# rev10.net
KiCad netlist of a schematic drawn in EAGLE
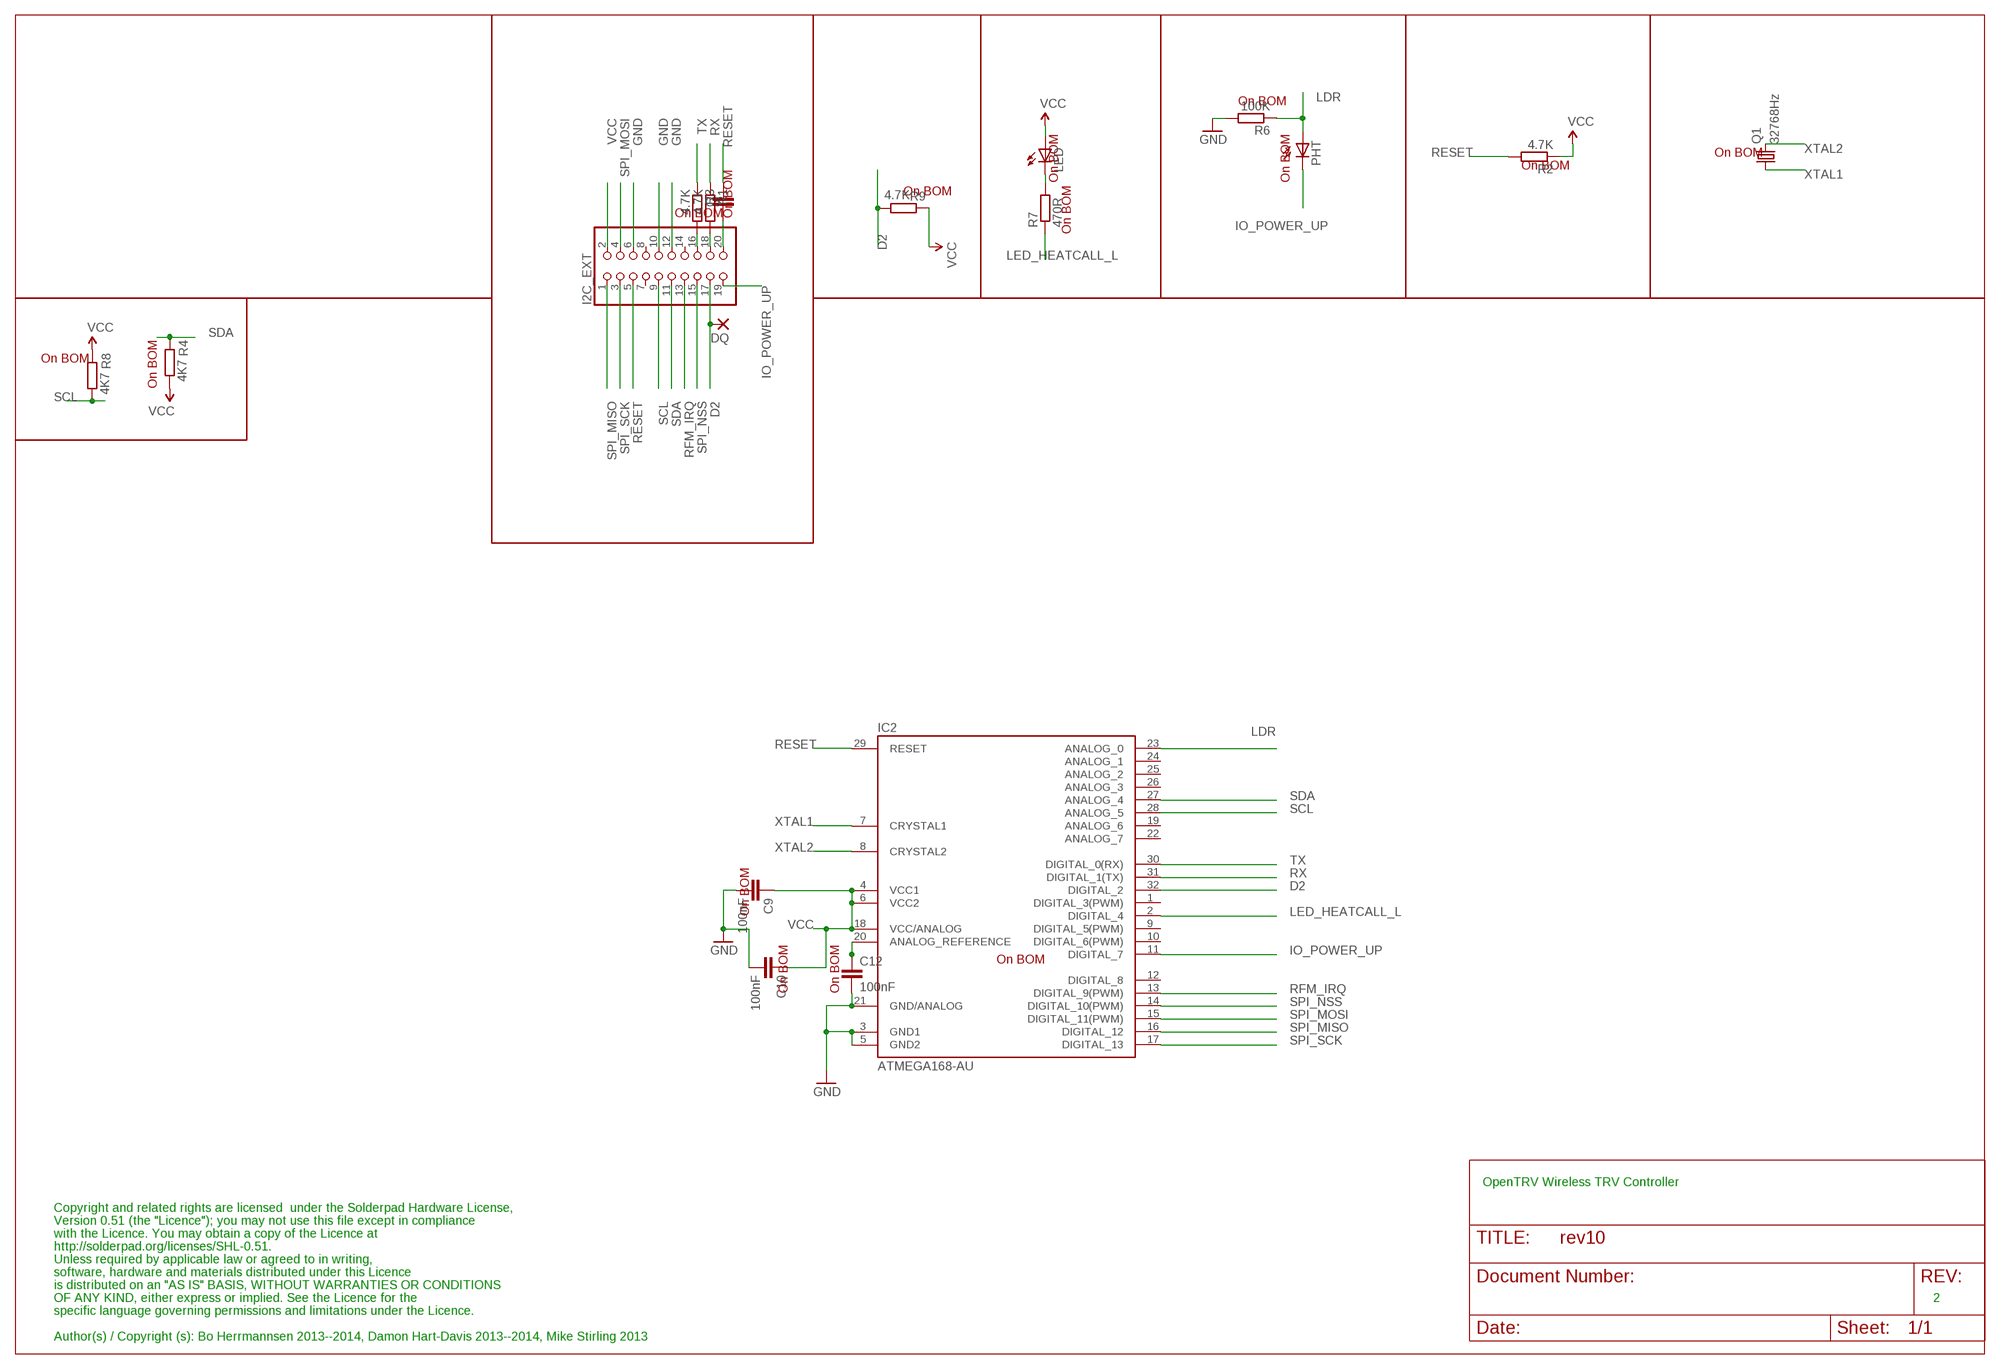
[diagram p0: schematic, sheet 1]

(export (version "E")
  (design (tool "Eeschema 10.0.6"))
  (components
    (comp (ref "C5")
      (value "100nF")
      (footprint "eagle-import:C0603")
      (libsource (lib "eagle-import") (part "C-EUC0603"))
    )
    (comp (ref "C9")
      (value "100nF")
      (footprint "eagle-import:C0603")
      (libsource (lib "eagle-import") (part "C-EUC0603"))
    )
    (comp (ref "C10")
      (value "100nF")
      (footprint "eagle-import:C0603")
      (libsource (lib "eagle-import") (part "C-EUC0603"))
    )
    (comp (ref "C12")
      (value "100nF")
      (footprint "eagle-import:C0603")
      (libsource (lib "eagle-import") (part "C-EUC0603"))
    )
    (comp (ref "DQ")
      (value "2,15/1,0")
      (footprint "eagle-import:2,15_1,0")
      (libsource (lib "eagle-import") (part "2,15/1,0"))
    )
    (comp (ref "I2C_EXT")
      (value "PINHD-2X10")
      (footprint "eagle-import:2X10")
      (libsource (lib "eagle-import") (part "PINHD-2X10"))
    )
    (comp (ref "IC2")
      (value "ATMEGA168-AU")
      (footprint "eagle-import:TQFP32-08")
      (libsource (lib "eagle-import") (part "ATMEGA168-AU"))
    )
    (comp (ref "LED")
      (value "LEDCHIP-LED0603")
      (footprint "eagle-import:CHIP-LED0603")
      (libsource (lib "eagle-import") (part "LEDCHIP-LED0603"))
    )
    (comp (ref "PHT")
      (value "BPX65")
      (footprint "eagle-import:BPX65")
      (fields (field (name "MPN") "BPX65."))
      (libsource (lib "eagle-import") (part "BPX65"))
    )
    (comp (ref "Q1")
      (value "32768Hz")
      (footprint "eagle-import:MC-306")
      (fields (field (name "MPN") "MC-306 60.0KHZ  100PPM ,12.5PF"))
      (libsource (lib "eagle-import") (part "MC-306"))
    )
    (comp (ref "R1")
      (value "4.7K")
      (footprint "eagle-import:R0603")
      (libsource (lib "eagle-import") (part "R-EU_R0603"))
    )
    (comp (ref "R2")
      (value "4.7K")
      (footprint "eagle-import:R0603")
      (libsource (lib "eagle-import") (part "R-EU_R0603"))
    )
    (comp (ref "R3")
      (value "4.7K")
      (footprint "eagle-import:R0603")
      (libsource (lib "eagle-import") (part "R-EU_R0603"))
    )
    (comp (ref "R4")
      (value "4K7")
      (footprint "eagle-import:R0603")
      (libsource (lib "eagle-import") (part "R-EU_R0603"))
    )
    (comp (ref "R6")
      (value "100K")
      (footprint "eagle-import:R0603")
      (libsource (lib "eagle-import") (part "R-EU_R0603"))
    )
    (comp (ref "R7")
      (value "470R")
      (footprint "eagle-import:R0603")
      (libsource (lib "eagle-import") (part "R-EU_R0603"))
    )
    (comp (ref "R8")
      (value "4K7")
      (footprint "eagle-import:R0603")
      (libsource (lib "eagle-import") (part "R-EU_R0603"))
    )
    (comp (ref "R9")
      (value "4.7K")
      (footprint "eagle-import:R0603")
      (libsource (lib "eagle-import") (part "R-EU_R0603"))
    )
  )
  (nets
    (net (code "1") (name "/D2") (class "Default")
      (node (ref "DQ") (pin "1") (pinfunction "P_1") (pintype "passive"))
      (node (ref "I2C_EXT") (pin "17") (pinfunction "17_17") (pintype "passive"))
      (node (ref "IC2") (pin "32") (pinfunction "DIGITAL_2_32") (pintype "bidirectional"))
      (node (ref "R9") (pin "1") (pinfunction "1_1") (pintype "passive"))
    )
    (net (code "2") (name "/IO_POWER_UP") (class "Default")
      (node (ref "I2C_EXT") (pin "19") (pinfunction "19_19") (pintype "passive"))
      (node (ref "IC2") (pin "11") (pinfunction "DIGITAL_7_11") (pintype "bidirectional"))
      (node (ref "PHT") (pin "K") (pinfunction "C_K") (pintype "passive"))
    )
    (net (code "3") (name "/LDR") (class "Default")
      (node (ref "IC2") (pin "23") (pinfunction "ANALOG_0_23") (pintype "bidirectional"))
      (node (ref "PHT") (pin "A") (pinfunction "A_A") (pintype "passive"))
      (node (ref "R6") (pin "1") (pinfunction "1_1") (pintype "passive"))
    )
    (net (code "4") (name "/LED_HEATCALL_L") (class "Default")
      (node (ref "IC2") (pin "2") (pinfunction "DIGITAL_4_2") (pintype "bidirectional"))
      (node (ref "R7") (pin "1") (pinfunction "1_1") (pintype "passive"))
    )
    (net (code "5") (name "/RESET") (class "Default")
      (node (ref "C5") (pin "1") (pinfunction "1_1") (pintype "passive"))
      (node (ref "I2C_EXT") (pin "5") (pinfunction "5_5") (pintype "passive"))
      (node (ref "IC2") (pin "29") (pinfunction "RESET_29") (pintype "bidirectional"))
      (node (ref "R2") (pin "2") (pinfunction "2_2") (pintype "passive"))
    )
    (net (code "6") (name "/RFM_IRQ") (class "Default")
      (node (ref "I2C_EXT") (pin "13") (pinfunction "13_13") (pintype "passive"))
      (node (ref "IC2") (pin "13") (pinfunction "DIGITAL_9(PWM)_13") (pintype "bidirectional"))
    )
    (net (code "7") (name "/RX") (class "Default")
      (node (ref "IC2") (pin "31") (pinfunction "DIGITAL_1(TX)_31") (pintype "bidirectional"))
      (node (ref "R1") (pin "1") (pinfunction "1_1") (pintype "passive"))
    )
    (net (code "8") (name "/SCL") (class "Default")
      (node (ref "I2C_EXT") (pin "9") (pinfunction "9_9") (pintype "passive"))
      (node (ref "IC2") (pin "28") (pinfunction "ANALOG_5_28") (pintype "bidirectional"))
      (node (ref "R8") (pin "1") (pinfunction "1_1") (pintype "passive"))
    )
    (net (code "9") (name "/SDA") (class "Default")
      (node (ref "I2C_EXT") (pin "11") (pinfunction "11_11") (pintype "passive"))
      (node (ref "IC2") (pin "27") (pinfunction "ANALOG_4_27") (pintype "bidirectional"))
      (node (ref "R4") (pin "2") (pinfunction "2_2") (pintype "passive"))
    )
    (net (code "10") (name "/SPI_MISO") (class "Default")
      (node (ref "I2C_EXT") (pin "1") (pinfunction "1_1") (pintype "passive"))
      (node (ref "IC2") (pin "16") (pinfunction "DIGITAL_12_16") (pintype "bidirectional"))
    )
    (net (code "11") (name "/SPI_MOSI") (class "Default")
      (node (ref "I2C_EXT") (pin "4") (pinfunction "4_4") (pintype "passive"))
      (node (ref "IC2") (pin "15") (pinfunction "DIGITAL_11(PWM)_15") (pintype "bidirectional"))
    )
    (net (code "12") (name "/SPI_NSS") (class "Default")
      (node (ref "I2C_EXT") (pin "15") (pinfunction "15_15") (pintype "passive"))
      (node (ref "IC2") (pin "14") (pinfunction "DIGITAL_10(PWM)_14") (pintype "bidirectional"))
    )
    (net (code "13") (name "/SPI_SCK") (class "Default")
      (node (ref "I2C_EXT") (pin "3") (pinfunction "3_3") (pintype "passive"))
      (node (ref "IC2") (pin "17") (pinfunction "DIGITAL_13_17") (pintype "bidirectional"))
    )
    (net (code "14") (name "/TX") (class "Default")
      (node (ref "IC2") (pin "30") (pinfunction "DIGITAL_0(RX)_30") (pintype "bidirectional"))
      (node (ref "R3") (pin "1") (pinfunction "1_1") (pintype "passive"))
    )
    (net (code "15") (name "/XTAL1") (class "Default")
      (node (ref "IC2") (pin "7") (pinfunction "CRYSTAL1_7") (pintype "bidirectional"))
      (node (ref "Q1") (pin "1") (pinfunction "1_1") (pintype "passive"))
    )
    (net (code "16") (name "/XTAL2") (class "Default")
      (node (ref "IC2") (pin "8") (pinfunction "CRYSTAL2_8") (pintype "bidirectional"))
      (node (ref "Q1") (pin "4") (pinfunction "2_4") (pintype "passive"))
    )
    (net (code "17") (name "GND") (class "Default")
      (node (ref "C10") (pin "2") (pinfunction "2_2") (pintype "passive"))
      (node (ref "C12") (pin "2") (pinfunction "2_2") (pintype "passive"))
      (node (ref "C9") (pin "2") (pinfunction "2_2") (pintype "passive"))
      (node (ref "I2C_EXT") (pin "10") (pinfunction "10_10") (pintype "passive"))
      (node (ref "I2C_EXT") (pin "12") (pinfunction "12_12") (pintype "passive"))
      (node (ref "I2C_EXT") (pin "6") (pinfunction "6_6") (pintype "passive"))
      (node (ref "IC2") (pin "21") (pinfunction "GND/ANALOG_21") (pintype "power_in"))
      (node (ref "IC2") (pin "3") (pinfunction "GND1_3") (pintype "power_in"))
      (node (ref "IC2") (pin "5") (pinfunction "GND2_5") (pintype "power_in"))
      (node (ref "R6") (pin "2") (pinfunction "2_2") (pintype "passive"))
    )
    (net (code "18") (name "Net-(C5-Pad2)") (class "Default")
      (node (ref "C5") (pin "2") (pinfunction "2_2") (pintype "passive"))
      (node (ref "I2C_EXT") (pin "20") (pinfunction "20_20") (pintype "passive"))
    )
    (net (code "19") (name "Net-(I2C_EXT-Pad16)") (class "Default")
      (node (ref "I2C_EXT") (pin "16") (pinfunction "16_16") (pintype "passive"))
      (node (ref "R3") (pin "2") (pinfunction "2_2") (pintype "passive"))
    )
    (net (code "20") (name "Net-(I2C_EXT-Pad18)") (class "Default")
      (node (ref "I2C_EXT") (pin "18") (pinfunction "18_18") (pintype "passive"))
      (node (ref "R1") (pin "2") (pinfunction "2_2") (pintype "passive"))
    )
    (net (code "21") (name "Net-(IC2-ANALOG_REFERENCE)") (class "Default")
      (node (ref "C12") (pin "1") (pinfunction "1_1") (pintype "passive"))
      (node (ref "IC2") (pin "20") (pinfunction "ANALOG_REFERENCE_20") (pintype "passive"))
    )
    (net (code "22") (name "Net-(LED-PadC)") (class "Default")
      (node (ref "LED") (pin "C") (pinfunction "C_C") (pintype "passive"))
      (node (ref "R7") (pin "2") (pinfunction "2_2") (pintype "passive"))
    )
    (net (code "23") (name "VCC") (class "Default")
      (node (ref "C10") (pin "1") (pinfunction "1_1") (pintype "passive"))
      (node (ref "C9") (pin "1") (pinfunction "1_1") (pintype "passive"))
      (node (ref "I2C_EXT") (pin "2") (pinfunction "2_2") (pintype "passive"))
      (node (ref "IC2") (pin "18") (pinfunction "VCC/ANALOG_18") (pintype "passive"))
      (node (ref "IC2") (pin "4") (pinfunction "VCC1_4") (pintype "power_in"))
      (node (ref "IC2") (pin "6") (pinfunction "VCC2_6") (pintype "power_in"))
      (node (ref "LED") (pin "A") (pinfunction "A_A") (pintype "passive"))
      (node (ref "R2") (pin "1") (pinfunction "1_1") (pintype "passive"))
      (node (ref "R4") (pin "1") (pinfunction "1_1") (pintype "passive"))
      (node (ref "R8") (pin "2") (pinfunction "2_2") (pintype "passive"))
      (node (ref "R9") (pin "2") (pinfunction "2_2") (pintype "passive"))
    )
    (net (code "24") (name "unconnected-(I2C_EXT-Pad7)") (class "Default")
      (node (ref "I2C_EXT") (pin "7") (pinfunction "7_7") (pintype "passive"))
    )
    (net (code "25") (name "unconnected-(I2C_EXT-Pad8)") (class "Default")
      (node (ref "I2C_EXT") (pin "8") (pinfunction "8_8") (pintype "passive"))
    )
    (net (code "26") (name "unconnected-(I2C_EXT-Pad14)") (class "Default")
      (node (ref "I2C_EXT") (pin "14") (pinfunction "14_14") (pintype "passive"))
    )
    (net (code "27") (name "unconnected-(IC2-ANALOG_1-Pad24)") (class "Default")
      (node (ref "IC2") (pin "24") (pinfunction "ANALOG_1_24") (pintype "bidirectional"))
    )
    (net (code "28") (name "unconnected-(IC2-ANALOG_2-Pad25)") (class "Default")
      (node (ref "IC2") (pin "25") (pinfunction "ANALOG_2_25") (pintype "bidirectional"))
    )
    (net (code "29") (name "unconnected-(IC2-ANALOG_3-Pad26)") (class "Default")
      (node (ref "IC2") (pin "26") (pinfunction "ANALOG_3_26") (pintype "bidirectional"))
    )
    (net (code "30") (name "unconnected-(IC2-ANALOG_6-Pad19)") (class "Default")
      (node (ref "IC2") (pin "19") (pinfunction "ANALOG_6_19") (pintype "passive"))
    )
    (net (code "31") (name "unconnected-(IC2-ANALOG_7-Pad22)") (class "Default")
      (node (ref "IC2") (pin "22") (pinfunction "ANALOG_7_22") (pintype "passive"))
    )
    (net (code "32") (name "unconnected-(IC2-DIGITAL_3(PWM)-Pad1)") (class "Default")
      (node (ref "IC2") (pin "1") (pinfunction "DIGITAL_3(PWM)_1") (pintype "bidirectional"))
    )
    (net (code "33") (name "unconnected-(IC2-DIGITAL_5(PWM)-Pad9)") (class "Default")
      (node (ref "IC2") (pin "9") (pinfunction "DIGITAL_5(PWM)_9") (pintype "bidirectional"))
    )
    (net (code "34") (name "unconnected-(IC2-DIGITAL_6(PWM)-Pad10)") (class "Default")
      (node (ref "IC2") (pin "10") (pinfunction "DIGITAL_6(PWM)_10") (pintype "bidirectional"))
    )
    (net (code "35") (name "unconnected-(IC2-DIGITAL_8-Pad12)") (class "Default")
      (node (ref "IC2") (pin "12") (pinfunction "DIGITAL_8_12") (pintype "bidirectional"))
    )
  )
)
